# Finishline_Display.net
KiCad netlist of a schematic drawn in EAGLE
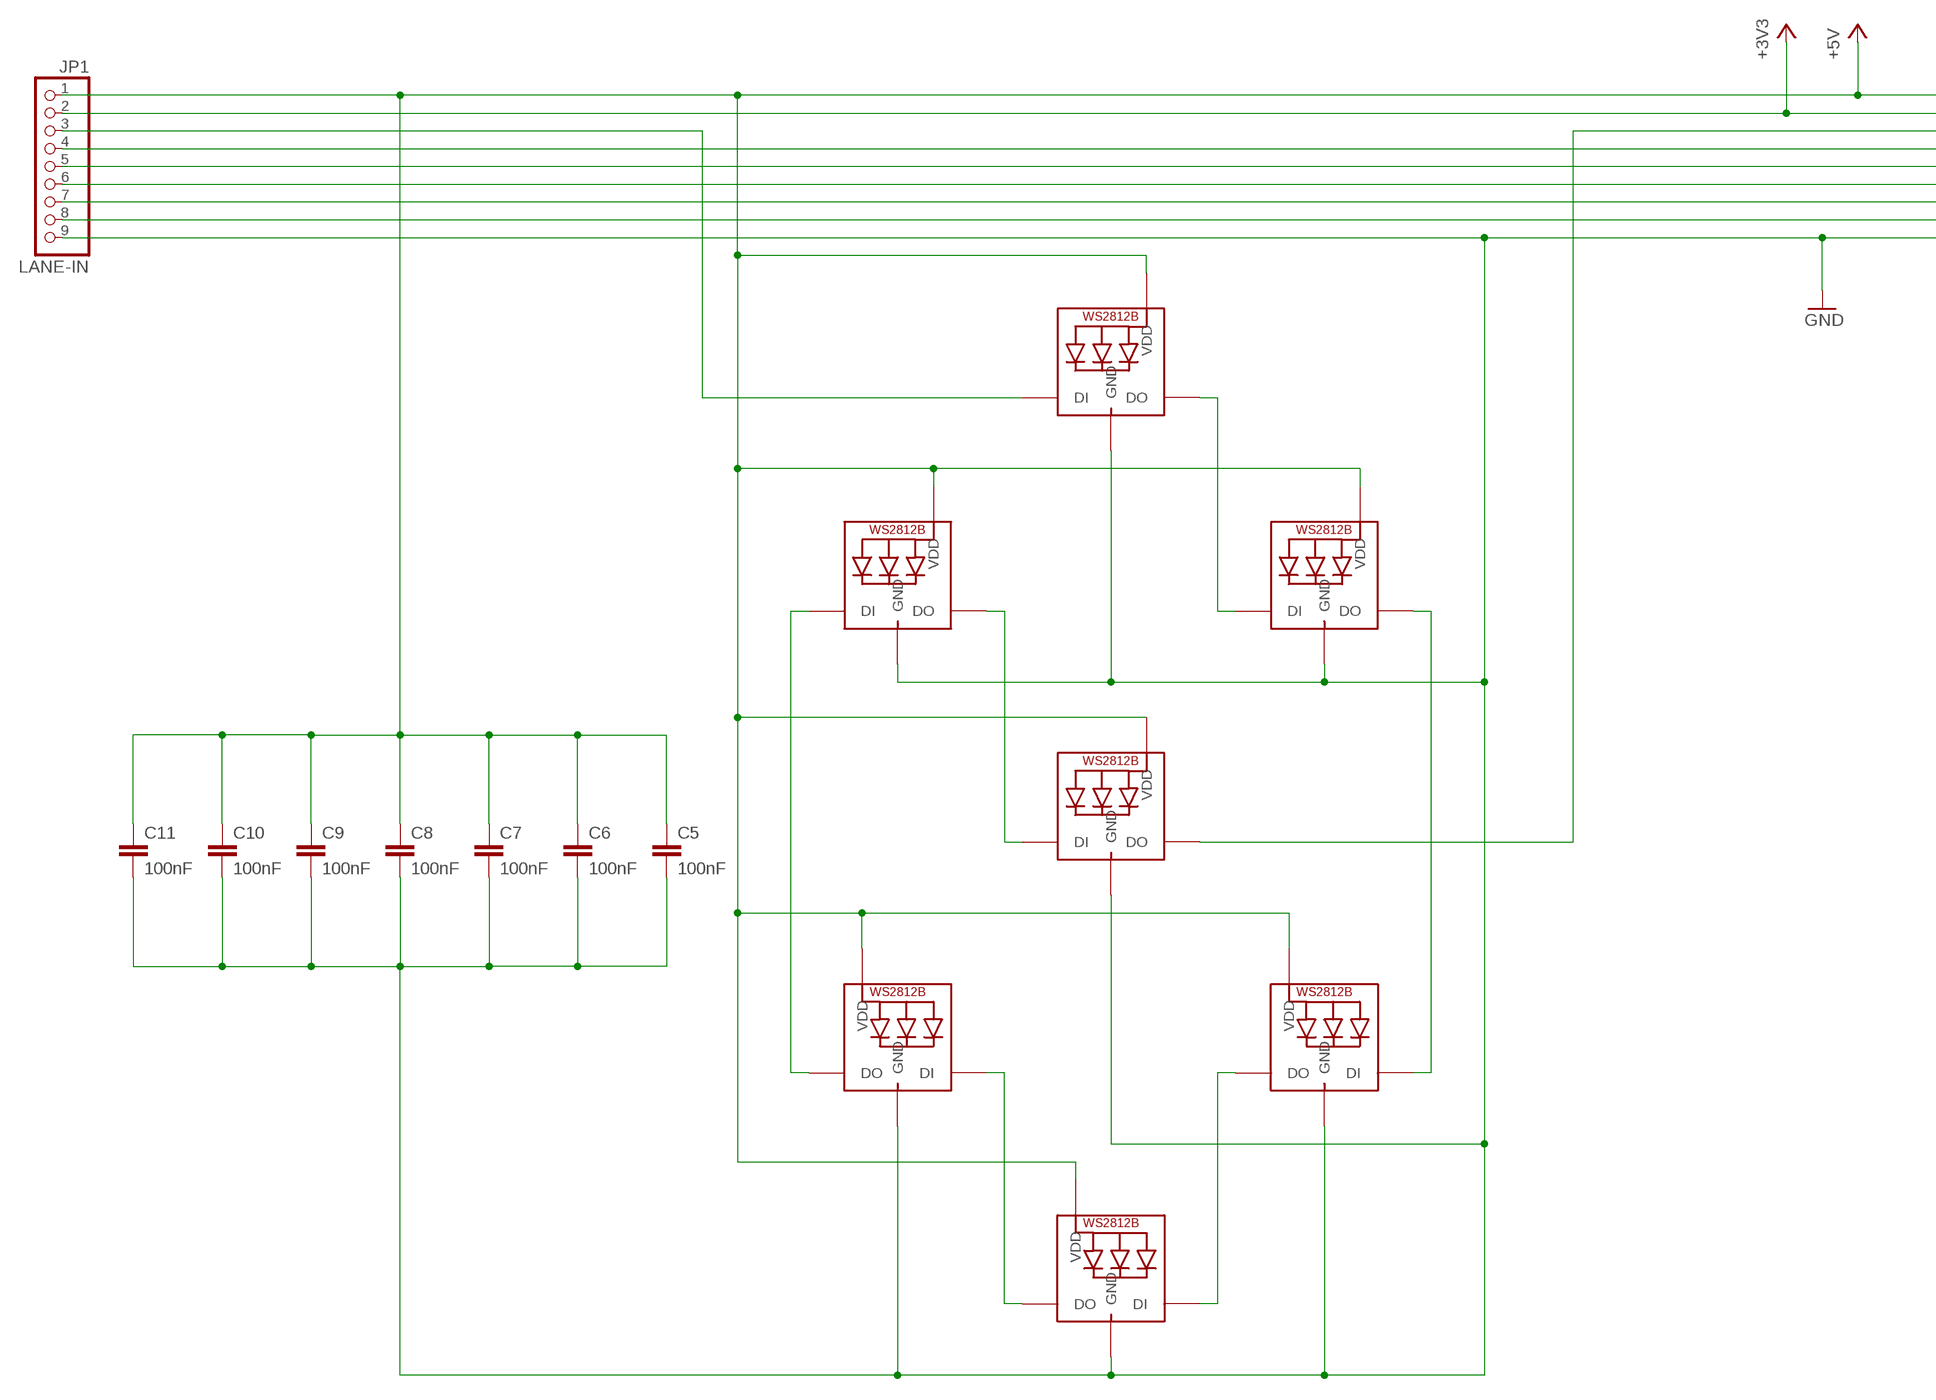
[diagram p0: schematic, sheet 1, part 1 of 2]
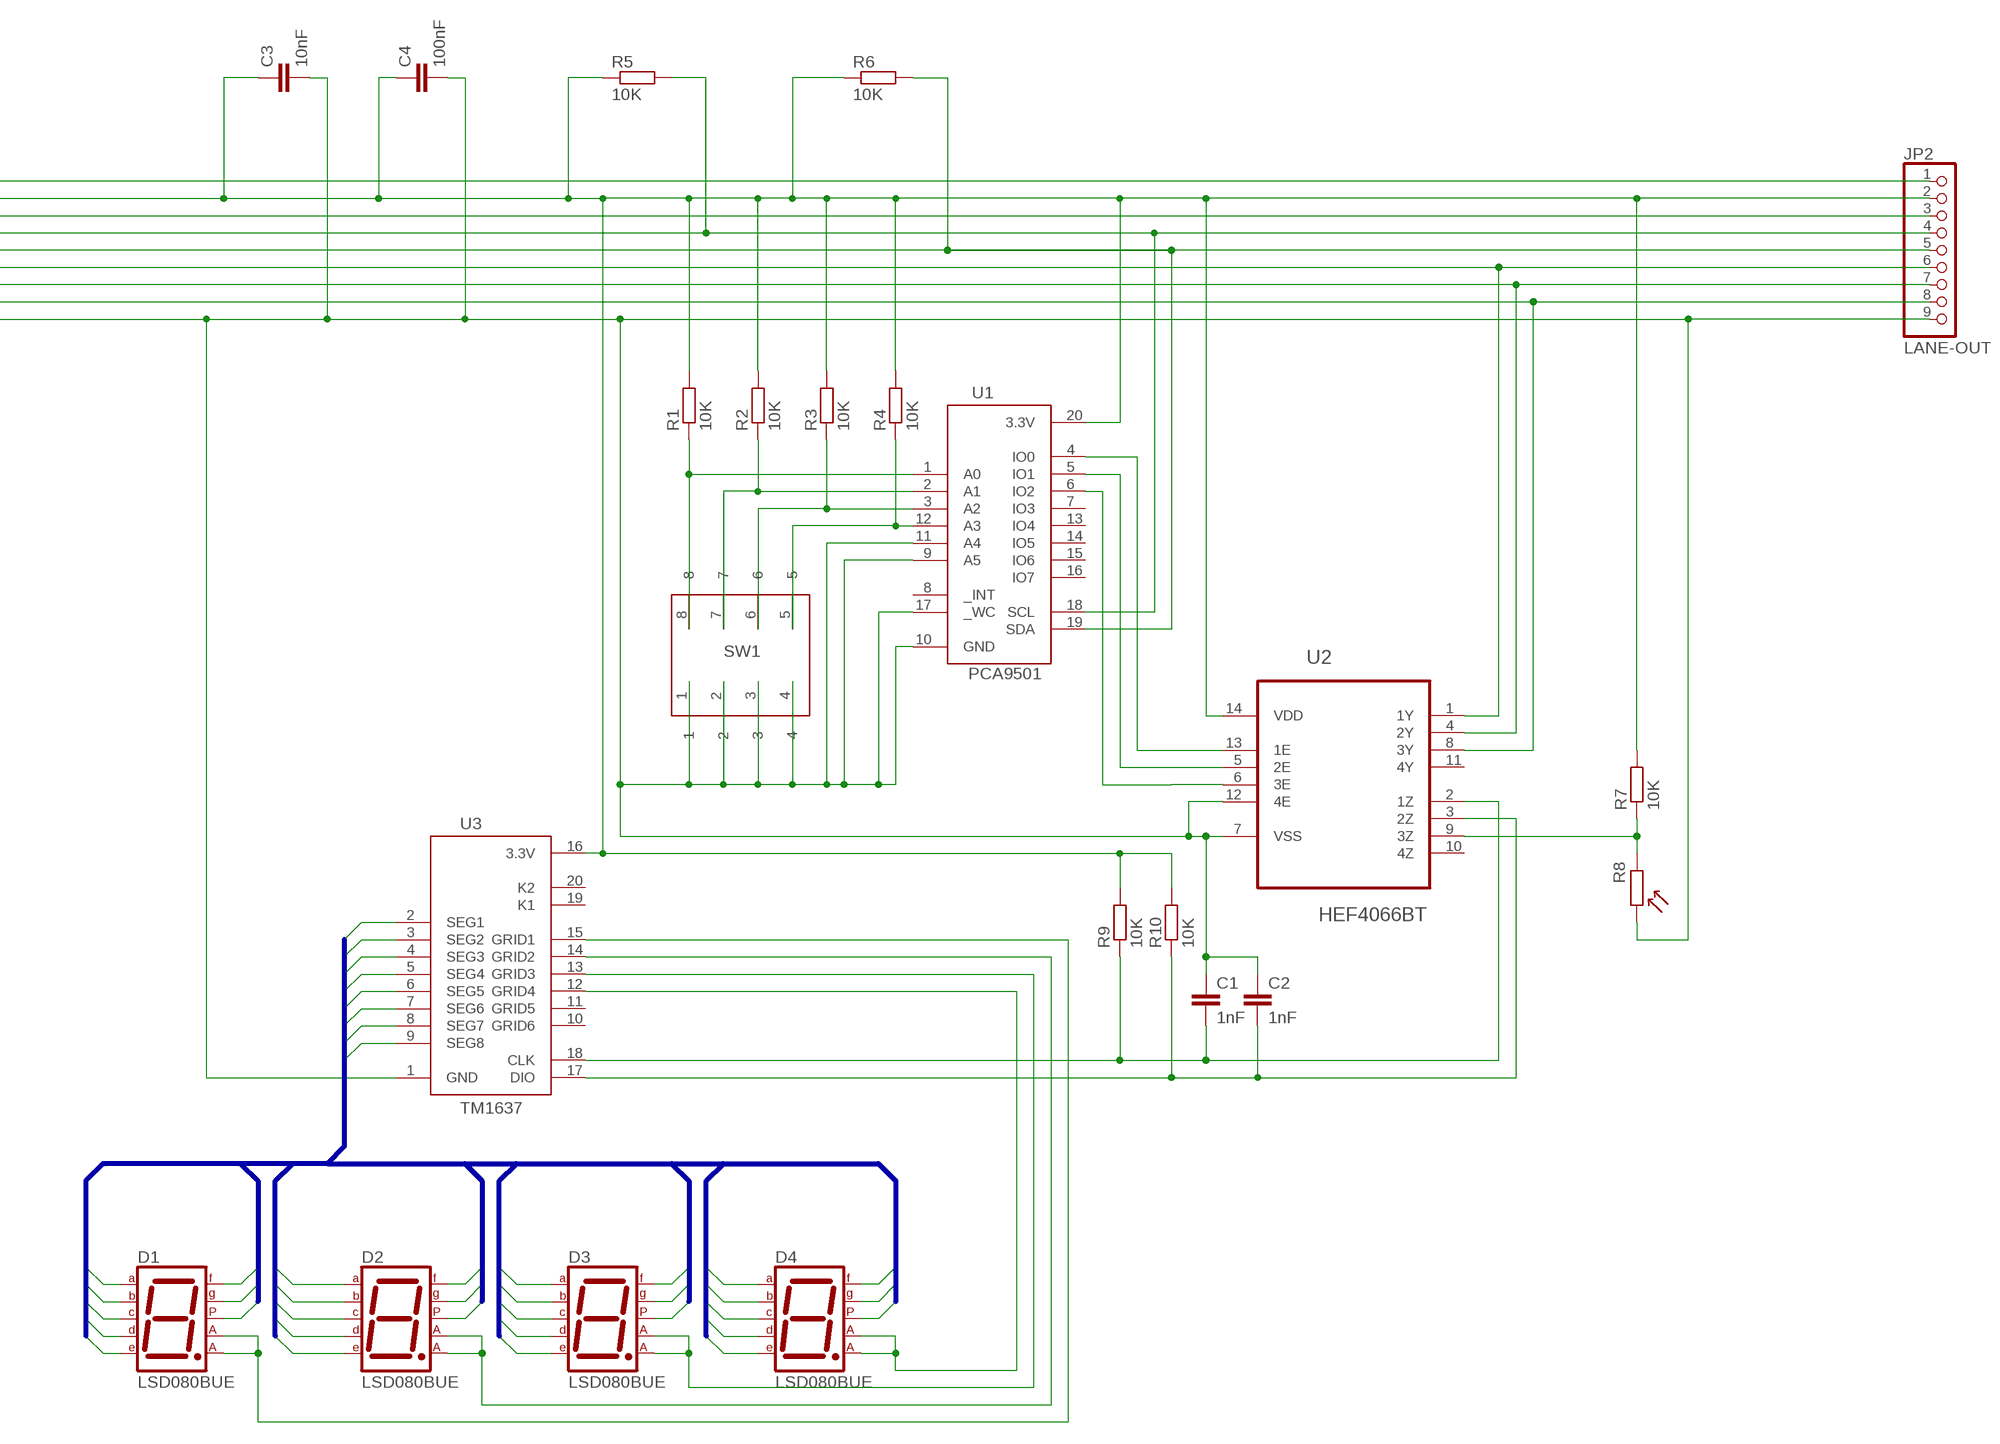
[diagram p1: schematic, sheet 1, part 2 of 2]

(export (version "E")
  (design (tool "Eeschema 10.0.6"))
  (components
    (comp (ref "C1")
      (value "1nF")
      (footprint "eagle-import:C0805")
      (libsource (lib "eagle-import") (part "C-EUC0805"))
    )
    (comp (ref "C2")
      (value "1nF")
      (footprint "eagle-import:C0805")
      (libsource (lib "eagle-import") (part "C-EUC0805"))
    )
    (comp (ref "C3")
      (value "10nF")
      (footprint "eagle-import:C0805")
      (libsource (lib "eagle-import") (part "C-EUC0805"))
    )
    (comp (ref "C4")
      (value "100nF")
      (footprint "eagle-import:C0805")
      (libsource (lib "eagle-import") (part "C-EUC0805"))
    )
    (comp (ref "C5")
      (value "100nF")
      (footprint "eagle-import:C0805")
      (libsource (lib "eagle-import") (part "C-EUC0805"))
    )
    (comp (ref "C6")
      (value "100nF")
      (footprint "eagle-import:C0805")
      (libsource (lib "eagle-import") (part "C-EUC0805"))
    )
    (comp (ref "C7")
      (value "100nF")
      (footprint "eagle-import:C0805")
      (libsource (lib "eagle-import") (part "C-EUC0805"))
    )
    (comp (ref "C8")
      (value "100nF")
      (footprint "eagle-import:C0805")
      (libsource (lib "eagle-import") (part "C-EUC0805"))
    )
    (comp (ref "C9")
      (value "100nF")
      (footprint "eagle-import:C0805")
      (libsource (lib "eagle-import") (part "C-EUC0805"))
    )
    (comp (ref "C10")
      (value "100nF")
      (footprint "eagle-import:C0805")
      (libsource (lib "eagle-import") (part "C-EUC0805"))
    )
    (comp (ref "C11")
      (value "100nF")
      (footprint "eagle-import:C0805")
      (libsource (lib "eagle-import") (part "C-EUC0805"))
    )
    (comp (ref "D1")
      (value "LSD080BUE")
      (footprint "eagle-import:7SEG-13")
      (libsource (lib "eagle-import") (part "7SEG-CA"))
    )
    (comp (ref "D2")
      (value "LSD080BUE")
      (footprint "eagle-import:7SEG-13")
      (libsource (lib "eagle-import") (part "7SEG-CA"))
    )
    (comp (ref "D3")
      (value "LSD080BUE")
      (footprint "eagle-import:7SEG-13")
      (libsource (lib "eagle-import") (part "7SEG-CA"))
    )
    (comp (ref "D4")
      (value "LSD080BUE")
      (footprint "eagle-import:7SEG-13")
      (libsource (lib "eagle-import") (part "7SEG-CA"))
    )
    (comp (ref "JP1")
      (value "LANE-IN")
      (footprint "eagle-import:1X09")
      (libsource (lib "eagle-import") (part "PINHD-1X9"))
    )
    (comp (ref "JP2")
      (value "LANE-OUT")
      (footprint "eagle-import:1X09")
      (libsource (lib "eagle-import") (part "PINHD-1X9"))
    )
    (comp (ref "LED1")
      (value "WS2812B5050")
      (footprint "eagle-import:WS2812B")
      (libsource (lib "eagle-import") (part "WS2812B5050"))
    )
    (comp (ref "LED2")
      (value "WS2812B5050")
      (footprint "eagle-import:WS2812B")
      (libsource (lib "eagle-import") (part "WS2812B5050"))
    )
    (comp (ref "LED3")
      (value "WS2812B5050")
      (footprint "eagle-import:WS2812B")
      (libsource (lib "eagle-import") (part "WS2812B5050"))
    )
    (comp (ref "LED4")
      (value "WS2812B5050")
      (footprint "eagle-import:WS2812B")
      (libsource (lib "eagle-import") (part "WS2812B5050"))
    )
    (comp (ref "LED5")
      (value "WS2812B5050")
      (footprint "eagle-import:WS2812B")
      (libsource (lib "eagle-import") (part "WS2812B5050"))
    )
    (comp (ref "LED6")
      (value "WS2812B5050")
      (footprint "eagle-import:WS2812B")
      (libsource (lib "eagle-import") (part "WS2812B5050"))
    )
    (comp (ref "LED7")
      (value "WS2812B5050")
      (footprint "eagle-import:WS2812B")
      (libsource (lib "eagle-import") (part "WS2812B5050"))
    )
    (comp (ref "R1")
      (value "10K")
      (footprint "eagle-import:M0805")
      (libsource (lib "eagle-import") (part "R-EU_M0805"))
    )
    (comp (ref "R2")
      (value "10K")
      (footprint "eagle-import:M0805")
      (libsource (lib "eagle-import") (part "R-EU_M0805"))
    )
    (comp (ref "R3")
      (value "10K")
      (footprint "eagle-import:M0805")
      (libsource (lib "eagle-import") (part "R-EU_M0805"))
    )
    (comp (ref "R4")
      (value "10K")
      (footprint "eagle-import:M0805")
      (libsource (lib "eagle-import") (part "R-EU_M0805"))
    )
    (comp (ref "R5")
      (value "10K")
      (footprint "eagle-import:M0805")
      (libsource (lib "eagle-import") (part "R-EU_M0805"))
    )
    (comp (ref "R6")
      (value "10K")
      (footprint "eagle-import:M0805")
      (libsource (lib "eagle-import") (part "R-EU_M0805"))
    )
    (comp (ref "R7")
      (value "10K")
      (footprint "eagle-import:M0805")
      (libsource (lib "eagle-import") (part "R-EU_M0805"))
    )
    (comp (ref "R8")
      (value "LDR 10K")
      (footprint "eagle-import:1X02")
      (libsource (lib "eagle-import") (part "LDR-TH"))
    )
    (comp (ref "R9")
      (value "10K")
      (footprint "eagle-import:M0805")
      (libsource (lib "eagle-import") (part "R-EU_M0805"))
    )
    (comp (ref "R10")
      (value "10K")
      (footprint "eagle-import:M0805")
      (libsource (lib "eagle-import") (part "R-EU_M0805"))
    )
    (comp (ref "SW1")
      (value "416131160804")
      (footprint "eagle-import:416131160804")
      (libsource (lib "eagle-import") (part "416131160804"))
    )
    (comp (ref "U1")
      (value "PCA9501")
      (footprint "eagle-import:SOIC127P1032X265-20N")
      (libsource (lib "eagle-import") (part "PCA9501"))
    )
    (comp (ref "U2")
      (value "HEF4066BT")
      (footprint "eagle-import:SOIC127P600X175-14N")
      (libsource (lib "eagle-import") (part "HEF4066BT"))
    )
    (comp (ref "U3")
      (value "TM1637")
      (footprint "eagle-import:SOIC127P1032X265-20N")
      (libsource (lib "eagle-import") (part "TM1637"))
    )
  )
  (nets
    (net (code "1") (name "+3V3") (class "Default")
      (node (ref "C3") (pin "1") (pinfunction "1_1") (pintype "passive"))
      (node (ref "C4") (pin "1") (pinfunction "1_1") (pintype "passive"))
      (node (ref "JP1") (pin "2") (pinfunction "2_2") (pintype "passive"))
      (node (ref "JP2") (pin "2") (pinfunction "2_2") (pintype "passive"))
      (node (ref "R1") (pin "2") (pinfunction "2_2") (pintype "passive"))
      (node (ref "R10") (pin "2") (pinfunction "2_2") (pintype "passive"))
      (node (ref "R2") (pin "2") (pinfunction "2_2") (pintype "passive"))
      (node (ref "R3") (pin "2") (pinfunction "2_2") (pintype "passive"))
      (node (ref "R4") (pin "2") (pinfunction "2_2") (pintype "passive"))
      (node (ref "R5") (pin "1") (pinfunction "1_1") (pintype "passive"))
      (node (ref "R6") (pin "1") (pinfunction "1_1") (pintype "passive"))
      (node (ref "R7") (pin "2") (pinfunction "2_2") (pintype "passive"))
      (node (ref "R9") (pin "2") (pinfunction "2_2") (pintype "passive"))
      (node (ref "U1") (pin "20") (pinfunction "3.3V_20") (pintype "passive"))
      (node (ref "U2") (pin "14") (pinfunction "VDD_14") (pintype "power_in"))
      (node (ref "U3") (pin "16") (pinfunction "3.3V_16") (pintype "bidirectional"))
    )
    (net (code "2") (name "+5V") (class "Default")
      (node (ref "C10") (pin "1") (pinfunction "1_1") (pintype "passive"))
      (node (ref "C11") (pin "1") (pinfunction "1_1") (pintype "passive"))
      (node (ref "C5") (pin "1") (pinfunction "1_1") (pintype "passive"))
      (node (ref "C6") (pin "1") (pinfunction "1_1") (pintype "passive"))
      (node (ref "C7") (pin "1") (pinfunction "1_1") (pintype "passive"))
      (node (ref "C8") (pin "1") (pinfunction "1_1") (pintype "passive"))
      (node (ref "C9") (pin "1") (pinfunction "1_1") (pintype "passive"))
      (node (ref "JP1") (pin "1") (pinfunction "1_1") (pintype "passive"))
      (node (ref "JP2") (pin "1") (pinfunction "1_1") (pintype "passive"))
      (node (ref "LED1") (pin "1-VDD") (pinfunction "VDD_1-VDD") (pintype "power_in"))
      (node (ref "LED2") (pin "1-VDD") (pinfunction "VDD_1-VDD") (pintype "power_in"))
      (node (ref "LED3") (pin "1-VDD") (pinfunction "VDD_1-VDD") (pintype "power_in"))
      (node (ref "LED4") (pin "1-VDD") (pinfunction "VDD_1-VDD") (pintype "power_in"))
      (node (ref "LED5") (pin "1-VDD") (pinfunction "VDD_1-VDD") (pintype "power_in"))
      (node (ref "LED6") (pin "1-VDD") (pinfunction "VDD_1-VDD") (pintype "power_in"))
      (node (ref "LED7") (pin "1-VDD") (pinfunction "VDD_1-VDD") (pintype "power_in"))
    )
    (net (code "3") (name "/SEG1") (class "Default")
      (node (ref "D1") (pin "7") (pinfunction "A_7") (pintype "passive"))
      (node (ref "D2") (pin "7") (pinfunction "A_7") (pintype "passive"))
      (node (ref "D3") (pin "7") (pinfunction "A_7") (pintype "passive"))
      (node (ref "D4") (pin "7") (pinfunction "A_7") (pintype "passive"))
      (node (ref "U3") (pin "2") (pinfunction "SEG1_2") (pintype "bidirectional"))
    )
    (net (code "4") (name "/SEG2") (class "Default")
      (node (ref "D1") (pin "6") (pinfunction "B_6") (pintype "passive"))
      (node (ref "D2") (pin "6") (pinfunction "B_6") (pintype "passive"))
      (node (ref "D3") (pin "6") (pinfunction "B_6") (pintype "passive"))
      (node (ref "D4") (pin "6") (pinfunction "B_6") (pintype "passive"))
      (node (ref "U3") (pin "3") (pinfunction "SEG2_3") (pintype "bidirectional"))
    )
    (net (code "5") (name "/SEG3") (class "Default")
      (node (ref "D1") (pin "4") (pinfunction "C_4") (pintype "passive"))
      (node (ref "D2") (pin "4") (pinfunction "C_4") (pintype "passive"))
      (node (ref "D3") (pin "4") (pinfunction "C_4") (pintype "passive"))
      (node (ref "D4") (pin "4") (pinfunction "C_4") (pintype "passive"))
      (node (ref "U3") (pin "4") (pinfunction "SEG3_4") (pintype "bidirectional"))
    )
    (net (code "6") (name "/SEG4") (class "Default")
      (node (ref "D1") (pin "2") (pinfunction "D_2") (pintype "passive"))
      (node (ref "D2") (pin "2") (pinfunction "D_2") (pintype "passive"))
      (node (ref "D3") (pin "2") (pinfunction "D_2") (pintype "passive"))
      (node (ref "D4") (pin "2") (pinfunction "D_2") (pintype "passive"))
      (node (ref "U3") (pin "5") (pinfunction "SEG4_5") (pintype "bidirectional"))
    )
    (net (code "7") (name "/SEG5") (class "Default")
      (node (ref "D1") (pin "1") (pinfunction "E_1") (pintype "passive"))
      (node (ref "D2") (pin "1") (pinfunction "E_1") (pintype "passive"))
      (node (ref "D3") (pin "1") (pinfunction "E_1") (pintype "passive"))
      (node (ref "D4") (pin "1") (pinfunction "E_1") (pintype "passive"))
      (node (ref "U3") (pin "6") (pinfunction "SEG5_6") (pintype "bidirectional"))
    )
    (net (code "8") (name "/SEG6") (class "Default")
      (node (ref "D1") (pin "9") (pinfunction "F_9") (pintype "passive"))
      (node (ref "D2") (pin "9") (pinfunction "F_9") (pintype "passive"))
      (node (ref "D3") (pin "9") (pinfunction "F_9") (pintype "passive"))
      (node (ref "D4") (pin "9") (pinfunction "F_9") (pintype "passive"))
      (node (ref "U3") (pin "7") (pinfunction "SEG6_7") (pintype "bidirectional"))
    )
    (net (code "9") (name "/SEG7") (class "Default")
      (node (ref "D1") (pin "10") (pinfunction "G_10") (pintype "passive"))
      (node (ref "D2") (pin "10") (pinfunction "G_10") (pintype "passive"))
      (node (ref "D3") (pin "10") (pinfunction "G_10") (pintype "passive"))
      (node (ref "D4") (pin "10") (pinfunction "G_10") (pintype "passive"))
      (node (ref "U3") (pin "8") (pinfunction "SEG7_8") (pintype "bidirectional"))
    )
    (net (code "10") (name "/SEG8") (class "Default")
      (node (ref "D1") (pin "5") (pinfunction "DP_5") (pintype "passive"))
      (node (ref "D2") (pin "5") (pinfunction "DP_5") (pintype "passive"))
      (node (ref "D3") (pin "5") (pinfunction "DP_5") (pintype "passive"))
      (node (ref "D4") (pin "5") (pinfunction "DP_5") (pintype "passive"))
      (node (ref "U3") (pin "9") (pinfunction "SEG8_9") (pintype "bidirectional"))
    )
    (net (code "11") (name "GND") (class "Default")
      (node (ref "C1") (pin "1") (pinfunction "1_1") (pintype "passive"))
      (node (ref "C10") (pin "2") (pinfunction "2_2") (pintype "passive"))
      (node (ref "C11") (pin "2") (pinfunction "2_2") (pintype "passive"))
      (node (ref "C2") (pin "1") (pinfunction "1_1") (pintype "passive"))
      (node (ref "C3") (pin "2") (pinfunction "2_2") (pintype "passive"))
      (node (ref "C4") (pin "2") (pinfunction "2_2") (pintype "passive"))
      (node (ref "C5") (pin "2") (pinfunction "2_2") (pintype "passive"))
      (node (ref "C6") (pin "2") (pinfunction "2_2") (pintype "passive"))
      (node (ref "C7") (pin "2") (pinfunction "2_2") (pintype "passive"))
      (node (ref "C8") (pin "2") (pinfunction "2_2") (pintype "passive"))
      (node (ref "C9") (pin "2") (pinfunction "2_2") (pintype "passive"))
      (node (ref "JP1") (pin "9") (pinfunction "9_9") (pintype "passive"))
      (node (ref "JP2") (pin "9") (pinfunction "9_9") (pintype "passive"))
      (node (ref "LED1") (pin "3-GND") (pinfunction "GND_3-GND") (pintype "power_in"))
      (node (ref "LED2") (pin "3-GND") (pinfunction "GND_3-GND") (pintype "power_in"))
      (node (ref "LED3") (pin "3-GND") (pinfunction "GND_3-GND") (pintype "power_in"))
      (node (ref "LED4") (pin "3-GND") (pinfunction "GND_3-GND") (pintype "power_in"))
      (node (ref "LED5") (pin "3-GND") (pinfunction "GND_3-GND") (pintype "power_in"))
      (node (ref "LED6") (pin "3-GND") (pinfunction "GND_3-GND") (pintype "power_in"))
      (node (ref "LED7") (pin "3-GND") (pinfunction "GND_3-GND") (pintype "power_in"))
      (node (ref "R8") (pin "2") (pinfunction "2_2") (pintype "passive"))
      (node (ref "SW1") (pin "1") (pinfunction "1_1") (pintype "bidirectional"))
      (node (ref "SW1") (pin "2") (pinfunction "2_2") (pintype "bidirectional"))
      (node (ref "SW1") (pin "3") (pinfunction "3_3") (pintype "bidirectional"))
      (node (ref "SW1") (pin "4") (pinfunction "4_4") (pintype "bidirectional"))
      (node (ref "U1") (pin "10") (pinfunction "GND_10") (pintype "passive"))
      (node (ref "U1") (pin "11") (pinfunction "A4_11") (pintype "bidirectional"))
      (node (ref "U1") (pin "17") (pinfunction "_WC_17") (pintype "bidirectional"))
      (node (ref "U1") (pin "9") (pinfunction "A5_9") (pintype "bidirectional"))
      (node (ref "U2") (pin "12") (pinfunction "4E_12") (pintype "input"))
      (node (ref "U2") (pin "7") (pinfunction "VSS_7") (pintype "passive"))
      (node (ref "U3") (pin "1") (pinfunction "GND_1") (pintype "bidirectional"))
    )
    (net (code "12") (name "Net-(D1-CA1)") (class "Default")
      (node (ref "D1") (pin "3") (pinfunction "CA1_3") (pintype "passive"))
      (node (ref "D1") (pin "8") (pinfunction "CA2_8") (pintype "passive"))
      (node (ref "U3") (pin "15") (pinfunction "GRID1_15") (pintype "bidirectional"))
    )
    (net (code "13") (name "Net-(D2-CA1)") (class "Default")
      (node (ref "D2") (pin "3") (pinfunction "CA1_3") (pintype "passive"))
      (node (ref "D2") (pin "8") (pinfunction "CA2_8") (pintype "passive"))
      (node (ref "U3") (pin "14") (pinfunction "GRID2_14") (pintype "bidirectional"))
    )
    (net (code "14") (name "Net-(D3-CA1)") (class "Default")
      (node (ref "D3") (pin "3") (pinfunction "CA1_3") (pintype "passive"))
      (node (ref "D3") (pin "8") (pinfunction "CA2_8") (pintype "passive"))
      (node (ref "U3") (pin "13") (pinfunction "GRID3_13") (pintype "bidirectional"))
    )
    (net (code "15") (name "Net-(D4-CA1)") (class "Default")
      (node (ref "D4") (pin "3") (pinfunction "CA1_3") (pintype "passive"))
      (node (ref "D4") (pin "8") (pinfunction "CA2_8") (pintype "passive"))
      (node (ref "U3") (pin "12") (pinfunction "GRID4_12") (pintype "bidirectional"))
    )
    (net (code "16") (name "Net-(LED1-DI)") (class "Default")
      (node (ref "JP1") (pin "3") (pinfunction "3_3") (pintype "passive"))
      (node (ref "LED1") (pin "4-DIN") (pinfunction "DI_4-DIN") (pintype "input"))
    )
    (net (code "17") (name "Net-(LED1-DO)") (class "Default")
      (node (ref "LED1") (pin "2-DOUT") (pinfunction "DO_2-DOUT") (pintype "output"))
      (node (ref "LED2") (pin "4-DIN") (pinfunction "DI_4-DIN") (pintype "input"))
    )
    (net (code "18") (name "Net-(LED2-DO)") (class "Default")
      (node (ref "LED2") (pin "2-DOUT") (pinfunction "DO_2-DOUT") (pintype "output"))
      (node (ref "LED3") (pin "4-DIN") (pinfunction "DI_4-DIN") (pintype "input"))
    )
    (net (code "19") (name "Net-(LED3-DO)") (class "Default")
      (node (ref "LED3") (pin "2-DOUT") (pinfunction "DO_2-DOUT") (pintype "output"))
      (node (ref "LED4") (pin "4-DIN") (pinfunction "DI_4-DIN") (pintype "input"))
    )
    (net (code "20") (name "Net-(LED4-DO)") (class "Default")
      (node (ref "LED4") (pin "2-DOUT") (pinfunction "DO_2-DOUT") (pintype "output"))
      (node (ref "LED5") (pin "4-DIN") (pinfunction "DI_4-DIN") (pintype "input"))
    )
    (net (code "21") (name "Net-(LED5-DO)") (class "Default")
      (node (ref "LED5") (pin "2-DOUT") (pinfunction "DO_2-DOUT") (pintype "output"))
      (node (ref "LED6") (pin "4-DIN") (pinfunction "DI_4-DIN") (pintype "input"))
    )
    (net (code "22") (name "Net-(LED6-DO)") (class "Default")
      (node (ref "LED6") (pin "2-DOUT") (pinfunction "DO_2-DOUT") (pintype "output"))
      (node (ref "LED7") (pin "4-DIN") (pinfunction "DI_4-DIN") (pintype "input"))
    )
    (net (code "23") (name "Net-(LED7-DO)") (class "Default")
      (node (ref "JP2") (pin "3") (pinfunction "3_3") (pintype "passive"))
      (node (ref "LED7") (pin "2-DOUT") (pinfunction "DO_2-DOUT") (pintype "output"))
    )
    (net (code "24") (name "Net-(U1-A0)") (class "Default")
      (node (ref "R1") (pin "1") (pinfunction "1_1") (pintype "passive"))
      (node (ref "SW1") (pin "8") (pinfunction "8_8") (pintype "bidirectional"))
      (node (ref "U1") (pin "1") (pinfunction "A0_1") (pintype "bidirectional"))
    )
    (net (code "25") (name "Net-(U1-A1)") (class "Default")
      (node (ref "R2") (pin "1") (pinfunction "1_1") (pintype "passive"))
      (node (ref "SW1") (pin "7") (pinfunction "7_7") (pintype "bidirectional"))
      (node (ref "U1") (pin "2") (pinfunction "A1_2") (pintype "bidirectional"))
    )
    (net (code "26") (name "Net-(U1-A2)") (class "Default")
      (node (ref "R3") (pin "1") (pinfunction "1_1") (pintype "passive"))
      (node (ref "SW1") (pin "6") (pinfunction "6_6") (pintype "bidirectional"))
      (node (ref "U1") (pin "3") (pinfunction "A2_3") (pintype "bidirectional"))
    )
    (net (code "27") (name "Net-(U1-A3)") (class "Default")
      (node (ref "R4") (pin "1") (pinfunction "1_1") (pintype "passive"))
      (node (ref "SW1") (pin "5") (pinfunction "5_5") (pintype "bidirectional"))
      (node (ref "U1") (pin "12") (pinfunction "A3_12") (pintype "bidirectional"))
    )
    (net (code "28") (name "Net-(U1-IO0)") (class "Default")
      (node (ref "U1") (pin "4") (pinfunction "IO0_4") (pintype "bidirectional"))
      (node (ref "U2") (pin "13") (pinfunction "1E_13") (pintype "input"))
    )
    (net (code "29") (name "Net-(U1-IO1)") (class "Default")
      (node (ref "U1") (pin "5") (pinfunction "IO1_5") (pintype "bidirectional"))
      (node (ref "U2") (pin "5") (pinfunction "2E_5") (pintype "input"))
    )
    (net (code "30") (name "Net-(U1-IO2)") (class "Default")
      (node (ref "U1") (pin "6") (pinfunction "IO2_6") (pintype "bidirectional"))
      (node (ref "U2") (pin "6") (pinfunction "3E_6") (pintype "input"))
    )
    (net (code "31") (name "Net-(U1-SCL)") (class "Default")
      (node (ref "JP1") (pin "4") (pinfunction "4_4") (pintype "passive"))
      (node (ref "JP2") (pin "4") (pinfunction "4_4") (pintype "passive"))
      (node (ref "R5") (pin "2") (pinfunction "2_2") (pintype "passive"))
      (node (ref "U1") (pin "18") (pinfunction "SCL_18") (pintype "bidirectional"))
    )
    (net (code "32") (name "Net-(U1-SDA)") (class "Default")
      (node (ref "JP1") (pin "5") (pinfunction "5_5") (pintype "passive"))
      (node (ref "JP2") (pin "5") (pinfunction "5_5") (pintype "passive"))
      (node (ref "R6") (pin "2") (pinfunction "2_2") (pintype "passive"))
      (node (ref "U1") (pin "19") (pinfunction "SDA_19") (pintype "bidirectional"))
    )
    (net (code "33") (name "Net-(U2-1Y)") (class "Default")
      (node (ref "JP1") (pin "6") (pinfunction "6_6") (pintype "passive"))
      (node (ref "JP2") (pin "6") (pinfunction "6_6") (pintype "passive"))
      (node (ref "U2") (pin "1") (pinfunction "1Y_1") (pintype "bidirectional"))
    )
    (net (code "34") (name "Net-(U2-1Z)") (class "Default")
      (node (ref "C1") (pin "2") (pinfunction "2_2") (pintype "passive"))
      (node (ref "R9") (pin "1") (pinfunction "1_1") (pintype "passive"))
      (node (ref "U2") (pin "2") (pinfunction "1Z_2") (pintype "bidirectional"))
      (node (ref "U3") (pin "18") (pinfunction "CLK_18") (pintype "bidirectional"))
    )
    (net (code "35") (name "Net-(U2-2Y)") (class "Default")
      (node (ref "JP1") (pin "7") (pinfunction "7_7") (pintype "passive"))
      (node (ref "JP2") (pin "7") (pinfunction "7_7") (pintype "passive"))
      (node (ref "U2") (pin "4") (pinfunction "2Y_4") (pintype "bidirectional"))
    )
    (net (code "36") (name "Net-(U2-2Z)") (class "Default")
      (node (ref "C2") (pin "2") (pinfunction "2_2") (pintype "passive"))
      (node (ref "R10") (pin "1") (pinfunction "1_1") (pintype "passive"))
      (node (ref "U2") (pin "3") (pinfunction "2Z_3") (pintype "bidirectional"))
      (node (ref "U3") (pin "17") (pinfunction "DIO_17") (pintype "bidirectional"))
    )
    (net (code "37") (name "Net-(U2-3Y)") (class "Default")
      (node (ref "JP1") (pin "8") (pinfunction "8_8") (pintype "passive"))
      (node (ref "JP2") (pin "8") (pinfunction "8_8") (pintype "passive"))
      (node (ref "U2") (pin "8") (pinfunction "3Y_8") (pintype "bidirectional"))
    )
    (net (code "38") (name "Net-(U2-3Z)") (class "Default")
      (node (ref "R7") (pin "1") (pinfunction "1_1") (pintype "passive"))
      (node (ref "R8") (pin "1") (pinfunction "1_1") (pintype "passive"))
      (node (ref "U2") (pin "9") (pinfunction "3Z_9") (pintype "bidirectional"))
    )
    (net (code "39") (name "unconnected-(U1-IO3-Pad7)") (class "Default")
      (node (ref "U1") (pin "7") (pinfunction "IO3_7") (pintype "bidirectional"))
    )
    (net (code "40") (name "unconnected-(U1-IO4-Pad13)") (class "Default")
      (node (ref "U1") (pin "13") (pinfunction "IO4_13") (pintype "bidirectional"))
    )
    (net (code "41") (name "unconnected-(U1-IO5-Pad14)") (class "Default")
      (node (ref "U1") (pin "14") (pinfunction "IO5_14") (pintype "bidirectional"))
    )
    (net (code "42") (name "unconnected-(U1-IO6-Pad15)") (class "Default")
      (node (ref "U1") (pin "15") (pinfunction "IO6_15") (pintype "bidirectional"))
    )
    (net (code "43") (name "unconnected-(U1-IO7-Pad16)") (class "Default")
      (node (ref "U1") (pin "16") (pinfunction "IO7_16") (pintype "bidirectional"))
    )
    (net (code "44") (name "unconnected-(U1-_INT-Pad8)") (class "Default")
      (node (ref "U1") (pin "8") (pinfunction "_INT_8") (pintype "bidirectional"))
    )
    (net (code "45") (name "unconnected-(U2-4Y-Pad11)") (class "Default")
      (node (ref "U2") (pin "11") (pinfunction "4Y_11") (pintype "bidirectional"))
    )
    (net (code "46") (name "unconnected-(U2-4Z-Pad10)") (class "Default")
      (node (ref "U2") (pin "10") (pinfunction "4Z_10") (pintype "bidirectional"))
    )
    (net (code "47") (name "unconnected-(U3-GRID5-Pad11)") (class "Default")
      (node (ref "U3") (pin "11") (pinfunction "GRID5_11") (pintype "bidirectional"))
    )
    (net (code "48") (name "unconnected-(U3-GRID6-Pad10)") (class "Default")
      (node (ref "U3") (pin "10") (pinfunction "GRID6_10") (pintype "bidirectional"))
    )
    (net (code "49") (name "unconnected-(U3-K1-Pad19)") (class "Default")
      (node (ref "U3") (pin "19") (pinfunction "K1_19") (pintype "bidirectional"))
    )
    (net (code "50") (name "unconnected-(U3-K2-Pad20)") (class "Default")
      (node (ref "U3") (pin "20") (pinfunction "K2_20") (pintype "bidirectional"))
    )
  )
)
